# spiro.net
KiCad netlist of a schematic drawn in EAGLE
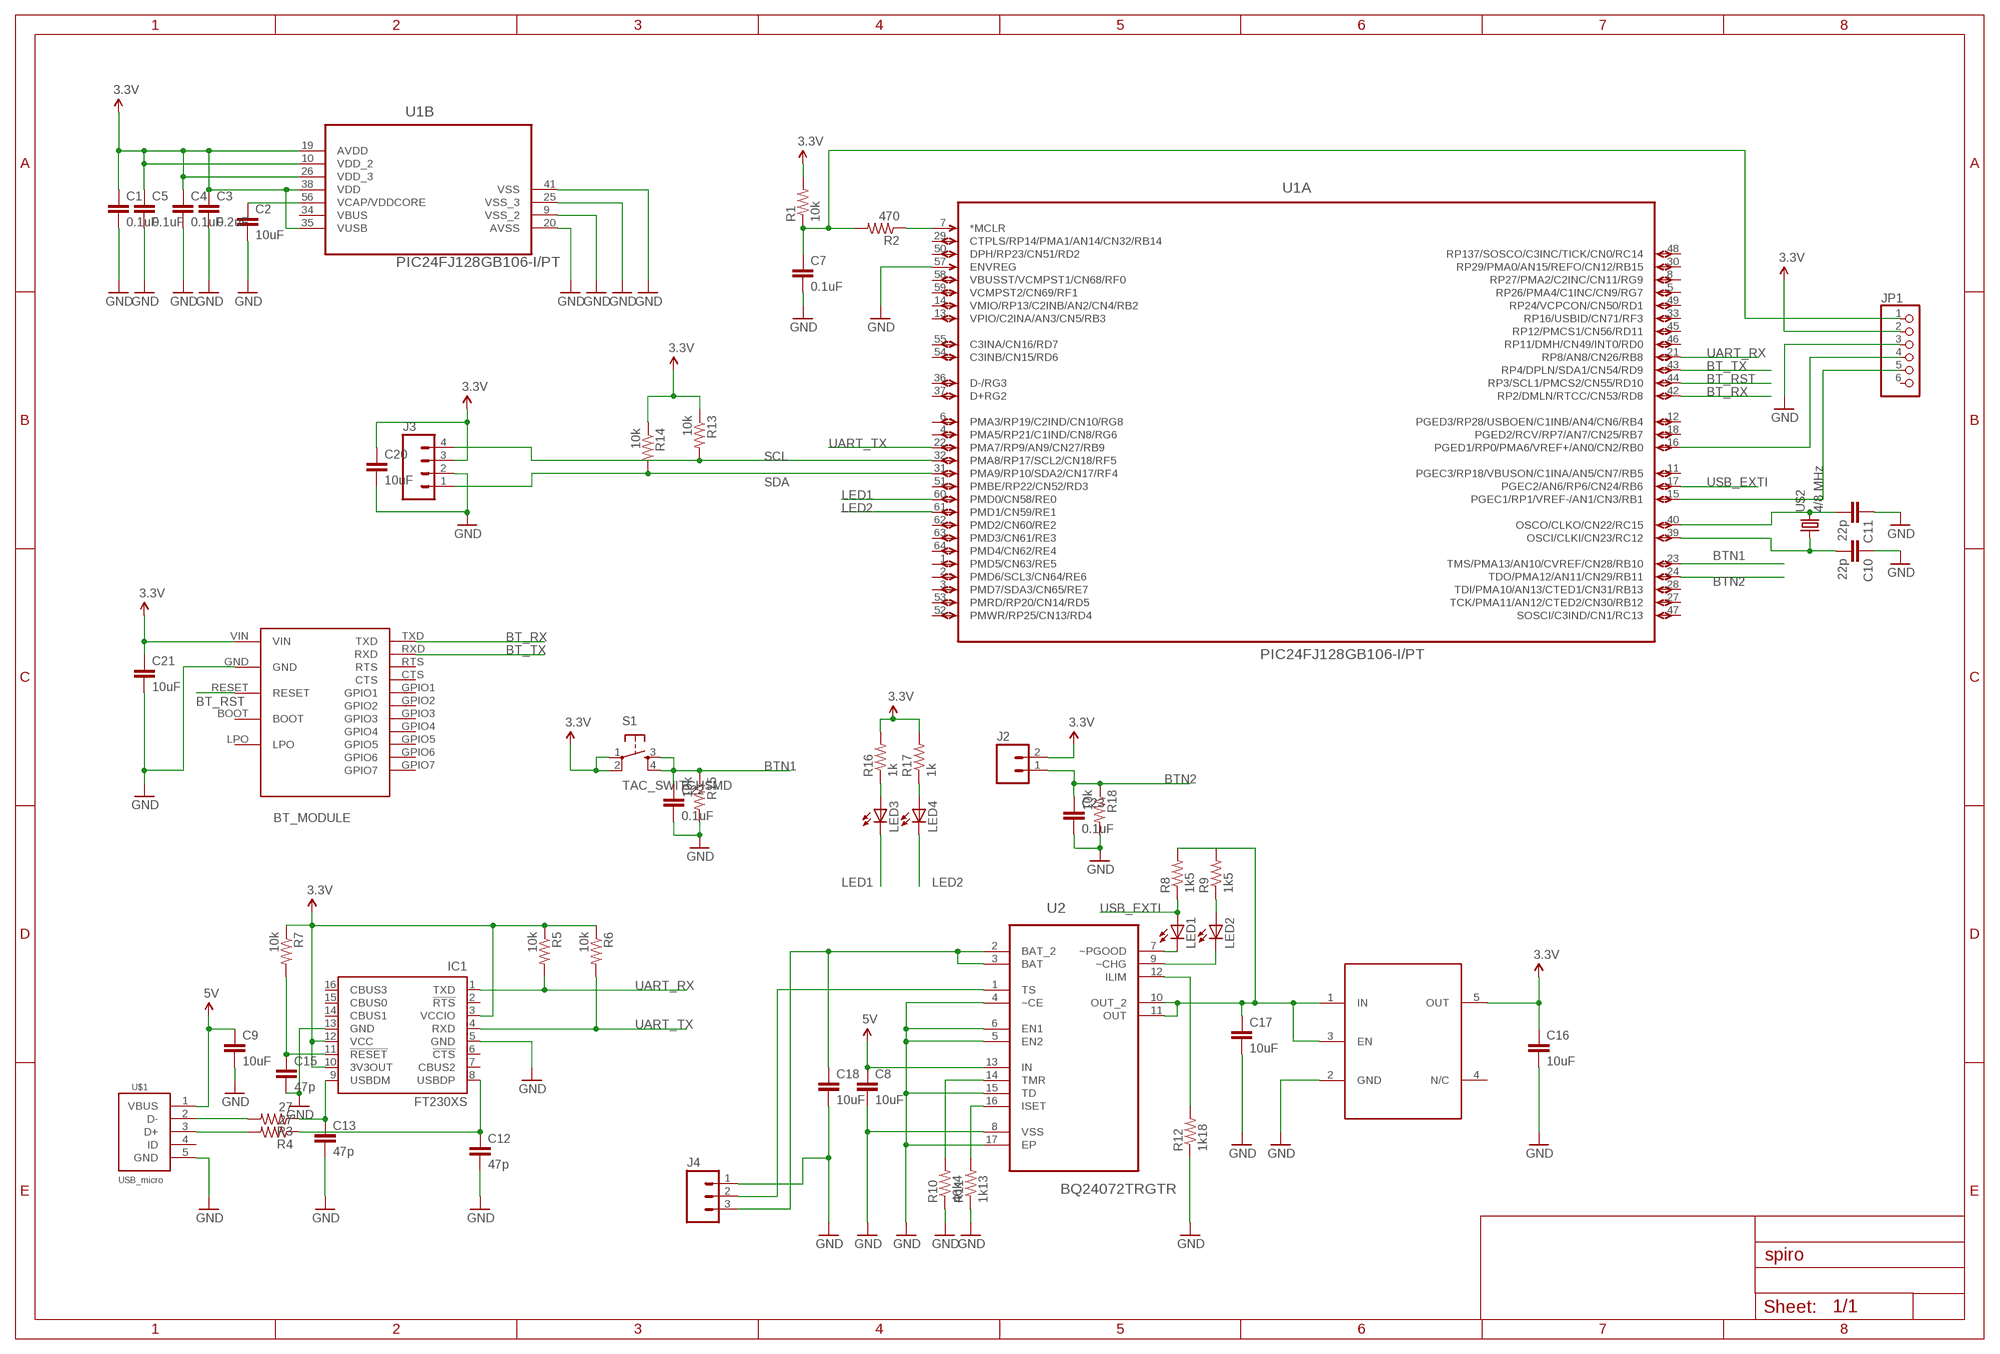
[diagram p0: schematic, sheet 1]

(export (version "E")
  (design (tool "Eeschema 10.0.6"))
  (components
    (comp (ref "BT_MODULE")
      (value "BT_MODULE")
      (footprint "eagle-import:SPBT2632C2A")
      (libsource (lib "eagle-import") (part "SPBT2632C2A"))
    )
    (comp (ref "C1")
      (value "0.1uF")
      (footprint "eagle-import:0603-CAP")
      (libsource (lib "eagle-import") (part "0.1UF-25V(+80/-20%)(0603)"))
    )
    (comp (ref "C2")
      (value "10uF")
      (footprint "eagle-import:1206")
      (libsource (lib "eagle-import") (part "10UF-6.3V-20%(1206)"))
    )
    (comp (ref "C3")
      (value "0.2uF")
      (footprint "eagle-import:0603-CAP")
      (libsource (lib "eagle-import") (part "0.1UF-25V(+80/-20%)(0603)"))
    )
    (comp (ref "C4")
      (value "0.1uF")
      (footprint "eagle-import:0603-CAP")
      (libsource (lib "eagle-import") (part "0.1UF-25V(+80/-20%)(0603)"))
    )
    (comp (ref "C5")
      (value "0.1uF")
      (footprint "eagle-import:0603-CAP")
      (libsource (lib "eagle-import") (part "0.1UF-25V(+80/-20%)(0603)"))
    )
    (comp (ref "C7")
      (value "0.1uF")
      (footprint "eagle-import:0603-CAP")
      (libsource (lib "eagle-import") (part "0.1UF-25V(+80/-20%)(0603)"))
    )
    (comp (ref "C8")
      (value "10uF")
      (footprint "eagle-import:1206")
      (libsource (lib "eagle-import") (part "10UF-6.3V-20%(1206)"))
    )
    (comp (ref "C9")
      (value "10uF")
      (footprint "eagle-import:1206")
      (libsource (lib "eagle-import") (part "10UF-6.3V-20%(1206)"))
    )
    (comp (ref "C10")
      (value "22p")
      (footprint "eagle-import:0603-CAP")
      (libsource (lib "eagle-import") (part "0.1UF-25V(+80/-20%)(0603)"))
    )
    (comp (ref "C11")
      (value "22p")
      (footprint "eagle-import:0603-CAP")
      (libsource (lib "eagle-import") (part "0.1UF-25V(+80/-20%)(0603)"))
    )
    (comp (ref "C12")
      (value "47p")
      (footprint "eagle-import:0603-CAP")
      (libsource (lib "eagle-import") (part "0.1UF-25V(+80/-20%)(0603)"))
    )
    (comp (ref "C13")
      (value "47p")
      (footprint "eagle-import:0603-CAP")
      (libsource (lib "eagle-import") (part "0.1UF-25V(+80/-20%)(0603)"))
    )
    (comp (ref "C15")
      (value "47p")
      (footprint "eagle-import:0603-CAP")
      (libsource (lib "eagle-import") (part "0.1UF-25V(+80/-20%)(0603)"))
    )
    (comp (ref "C16")
      (value "10uF")
      (footprint "eagle-import:1206")
      (libsource (lib "eagle-import") (part "10UF-6.3V-20%(1206)"))
    )
    (comp (ref "C17")
      (value "10uF")
      (footprint "eagle-import:1206")
      (libsource (lib "eagle-import") (part "10UF-6.3V-20%(1206)"))
    )
    (comp (ref "C18")
      (value "10uF")
      (footprint "eagle-import:1206")
      (libsource (lib "eagle-import") (part "10UF-6.3V-20%(1206)"))
    )
    (comp (ref "C20")
      (value "10uF")
      (footprint "eagle-import:1206")
      (libsource (lib "eagle-import") (part "10UF-6.3V-20%(1206)"))
    )
    (comp (ref "C21")
      (value "10uF")
      (footprint "eagle-import:1206")
      (libsource (lib "eagle-import") (part "10UF-6.3V-20%(1206)"))
    )
    (comp (ref "C22")
      (value "0.1uF")
      (footprint "eagle-import:0603-CAP")
      (libsource (lib "eagle-import") (part "0.1UF-25V(+80/-20%)(0603)"))
    )
    (comp (ref "C23")
      (value "0.1uF")
      (footprint "eagle-import:0603-CAP")
      (libsource (lib "eagle-import") (part "0.1UF-25V(+80/-20%)(0603)"))
    )
    (comp (ref "IC1")
      (value "FT230XS")
      (footprint "eagle-import:SSOP16")
      (libsource (lib "eagle-import") (part "FT230XS"))
    )
    (comp (ref "J2")
      (value "M02PTH")
      (footprint "eagle-import:1X02")
      (libsource (lib "eagle-import") (part "M02PTH"))
    )
    (comp (ref "J3")
      (value "M04NO_SILK_ALL_ROUND")
      (footprint "eagle-import:1X04_NO_SILK_ALL_ROUND")
      (libsource (lib "eagle-import") (part "M04NO_SILK_ALL_ROUND"))
    )
    (comp (ref "J4")
      (value "M03")
      (footprint "eagle-import:1X03-SMD-50MILS")
      (libsource (lib "eagle-import") (part "M03"))
    )
    (comp (ref "JP1")
      (value "PINHD-1X6")
      (footprint "eagle-import:1X06")
      (libsource (lib "eagle-import") (part "PINHD-1X6"))
    )
    (comp (ref "LED1")
      (value "LEDCHIP-LED0603")
      (footprint "eagle-import:CHIP-LED0603")
      (libsource (lib "eagle-import") (part "LEDCHIP-LED0603"))
    )
    (comp (ref "LED2")
      (value "LEDCHIP-LED0603")
      (footprint "eagle-import:CHIP-LED0603")
      (libsource (lib "eagle-import") (part "LEDCHIP-LED0603"))
    )
    (comp (ref "LED3")
      (value "LEDCHIP-LED0603")
      (footprint "eagle-import:CHIP-LED0603")
      (libsource (lib "eagle-import") (part "LEDCHIP-LED0603"))
    )
    (comp (ref "LED4")
      (value "LEDCHIP-LED0603")
      (footprint "eagle-import:CHIP-LED0603")
      (libsource (lib "eagle-import") (part "LEDCHIP-LED0603"))
    )
    (comp (ref "R1")
      (value "10k")
      (footprint "eagle-import:0603-RES")
      (libsource (lib "eagle-import") (part "RESISTOR0603-RES"))
    )
    (comp (ref "R2")
      (value "470")
      (footprint "eagle-import:0603-RES")
      (libsource (lib "eagle-import") (part "RESISTOR0603-RES"))
    )
    (comp (ref "R3")
      (value "27")
      (footprint "eagle-import:0603-RES")
      (libsource (lib "eagle-import") (part "RESISTOR0603-RES"))
    )
    (comp (ref "R4")
      (value "27")
      (footprint "eagle-import:0603-RES")
      (libsource (lib "eagle-import") (part "RESISTOR0603-RES"))
    )
    (comp (ref "R5")
      (value "10k")
      (footprint "eagle-import:0603-RES")
      (libsource (lib "eagle-import") (part "RESISTOR0603-RES"))
    )
    (comp (ref "R6")
      (value "10k")
      (footprint "eagle-import:0603-RES")
      (libsource (lib "eagle-import") (part "RESISTOR0603-RES"))
    )
    (comp (ref "R7")
      (value "10k")
      (footprint "eagle-import:0603-RES")
      (libsource (lib "eagle-import") (part "RESISTOR0603-RES"))
    )
    (comp (ref "R8")
      (value "1k5")
      (footprint "eagle-import:0603-RES")
      (libsource (lib "eagle-import") (part "RESISTOR0603-RES"))
    )
    (comp (ref "R9")
      (value "1k5")
      (footprint "eagle-import:0603-RES")
      (libsource (lib "eagle-import") (part "RESISTOR0603-RES"))
    )
    (comp (ref "R10")
      (value "46k4")
      (footprint "eagle-import:0603-RES")
      (libsource (lib "eagle-import") (part "RESISTOR0603-RES"))
    )
    (comp (ref "R11")
      (value "1k13")
      (footprint "eagle-import:0603-RES")
      (libsource (lib "eagle-import") (part "RESISTOR0603-RES"))
    )
    (comp (ref "R12")
      (value "1k18")
      (footprint "eagle-import:0603-RES")
      (libsource (lib "eagle-import") (part "RESISTOR0603-RES"))
    )
    (comp (ref "R13")
      (value "10k")
      (footprint "eagle-import:0603-RES")
      (libsource (lib "eagle-import") (part "RESISTOR0603-RES"))
    )
    (comp (ref "R14")
      (value "10k")
      (footprint "eagle-import:0603-RES")
      (libsource (lib "eagle-import") (part "RESISTOR0603-RES"))
    )
    (comp (ref "R15")
      (value "10k")
      (footprint "eagle-import:0603-RES")
      (libsource (lib "eagle-import") (part "RESISTOR0603-RES"))
    )
    (comp (ref "R16")
      (value "1k")
      (footprint "eagle-import:0603-RES")
      (libsource (lib "eagle-import") (part "RESISTOR0603-RES"))
    )
    (comp (ref "R17")
      (value "1k")
      (footprint "eagle-import:0603-RES")
      (libsource (lib "eagle-import") (part "RESISTOR0603-RES"))
    )
    (comp (ref "R18")
      (value "10k")
      (footprint "eagle-import:0603-RES")
      (libsource (lib "eagle-import") (part "RESISTOR0603-RES"))
    )
    (comp (ref "S1")
      (value "TAC_SWITCHSMD")
      (footprint "eagle-import:TACTILE-SWITCH-SMD")
      (libsource (lib "eagle-import") (part "TAC_SWITCHSMD"))
    )
    (comp (ref "U$1")
      (value "USB_micro")
      (footprint "eagle-import:USB-MICRO-MOLEX-105017-0001")
      (libsource (lib "eagle-import") (part "USB-CON-5PIN-105017-0001"))
    )
    (comp (ref "U$2")
      (value "4/8 MHz")
      (footprint "eagle-import:CRYSTAL-SMD-6X3.5-2SMX")
      (libsource (lib "eagle-import") (part "CRYSTAL-2SMX"))
    )
    (comp (ref "U$3")
      (value "LP3990")
      (footprint "eagle-import:SOT95P280X145-5N")
      (libsource (lib "eagle-import") (part "LP3990"))
    )
    (comp (ref "U1")
      (value "PIC24FJ128GB106-I/PT")
      (footprint "eagle-import:QFP50P1200X1200X120-64N")
      (fields (field (name "MPN") "PIC24FJ128Gb106-I/PT"))
      (libsource (lib "eagle-import") (part "PIC24FJ128GB106-I/PT"))
    )
    (comp (ref "U2")
      (value "BQ24072TRGTR")
      (footprint "eagle-import:QFN50P300X300X100-17N")
      (libsource (lib "eagle-import") (part "BQ24072TRGTR"))
    )
  )
  (nets
    (net (code "1") (name "/BTN1") (class "Default")
      (node (ref "C22") (pin "1") (pinfunction "1_1") (pintype "passive"))
      (node (ref "R15") (pin "1") (pinfunction "1_1") (pintype "passive"))
      (node (ref "S1") (pin "3") (pinfunction "3_3") (pintype "passive"))
      (node (ref "S1") (pin "4") (pinfunction "4_4") (pintype "passive"))
      (node (ref "U1") (pin "23") (pinfunction "TMS/PMA13/AN10/CVREF/CN28/RB10_23") (pintype "bidirectional"))
    )
    (net (code "2") (name "/BTN2") (class "Default")
      (node (ref "C23") (pin "1") (pinfunction "1_1") (pintype "passive"))
      (node (ref "J2") (pin "1") (pinfunction "1_1") (pintype "passive"))
      (node (ref "R18") (pin "1") (pinfunction "1_1") (pintype "passive"))
      (node (ref "U1") (pin "24") (pinfunction "TDO/PMA12/AN11/CN29/RB11_24") (pintype "bidirectional"))
    )
    (net (code "3") (name "/BT_RST") (class "Default")
      (node (ref "BT_MODULE") (pin "RESET") (pinfunction "RESET_RESET") (pintype "bidirectional"))
      (node (ref "U1") (pin "44") (pinfunction "RP3/SCL1/PMCS2/CN55/RD10_44") (pintype "bidirectional"))
    )
    (net (code "4") (name "/BT_RX") (class "Default")
      (node (ref "BT_MODULE") (pin "TXD") (pinfunction "TXD_TXD") (pintype "bidirectional"))
      (node (ref "U1") (pin "42") (pinfunction "RP2/DMLN/RTCC/CN53/RD8_42") (pintype "bidirectional"))
    )
    (net (code "5") (name "/BT_TX") (class "Default")
      (node (ref "BT_MODULE") (pin "RXD") (pinfunction "RXD_RXD") (pintype "bidirectional"))
      (node (ref "U1") (pin "43") (pinfunction "RP4/DPLN/SDA1/CN54/RD9_43") (pintype "bidirectional"))
    )
    (net (code "6") (name "/LED1") (class "Default")
      (node (ref "LED3") (pin "C") (pinfunction "C_C") (pintype "passive"))
      (node (ref "U1") (pin "60") (pinfunction "PMD0/CN58/RE0_60") (pintype "bidirectional"))
    )
    (net (code "7") (name "/LED2") (class "Default")
      (node (ref "LED4") (pin "C") (pinfunction "C_C") (pintype "passive"))
      (node (ref "U1") (pin "61") (pinfunction "PMD1/CN59/RE1_61") (pintype "bidirectional"))
    )
    (net (code "8") (name "/SCL") (class "Default")
      (node (ref "J3") (pin "4") (pinfunction "4_4") (pintype "passive"))
      (node (ref "R13") (pin "2") (pinfunction "2_2") (pintype "passive"))
      (node (ref "U1") (pin "32") (pinfunction "PMA8/RP17/SCL2/CN18/RF5_32") (pintype "bidirectional"))
    )
    (net (code "9") (name "/SDA") (class "Default")
      (node (ref "J3") (pin "1") (pinfunction "1_1") (pintype "passive"))
      (node (ref "R14") (pin "2") (pinfunction "2_2") (pintype "passive"))
      (node (ref "U1") (pin "31") (pinfunction "PMA9/RP10/SDA2/CN17/RF4_31") (pintype "bidirectional"))
    )
    (net (code "10") (name "/UART_RX") (class "Default")
      (node (ref "IC1") (pin "1") (pinfunction "TXD_1") (pintype "output"))
      (node (ref "R5") (pin "2") (pinfunction "2_2") (pintype "passive"))
      (node (ref "U1") (pin "21") (pinfunction "RP8/AN8/CN26/RB8_21") (pintype "bidirectional"))
    )
    (net (code "11") (name "/UART_TX") (class "Default")
      (node (ref "IC1") (pin "4") (pinfunction "RXD_4") (pintype "input"))
      (node (ref "R6") (pin "2") (pinfunction "2_2") (pintype "passive"))
      (node (ref "U1") (pin "22") (pinfunction "PMA7/RP9/AN9/CN27/RB9_22") (pintype "bidirectional"))
    )
    (net (code "12") (name "/USB_EXTI") (class "Default")
      (node (ref "LED1") (pin "A") (pinfunction "A_A") (pintype "passive"))
      (node (ref "R8") (pin "1") (pinfunction "1_1") (pintype "passive"))
      (node (ref "U1") (pin "17") (pinfunction "PGEC2/AN6/RP6/CN24/RB6_17") (pintype "bidirectional"))
    )
    (net (code "13") (name "/VBUS") (class "Default")
      (node (ref "U1") (pin "34") (pinfunction "VBUS_34") (pintype "power_in"))
    )
    (net (code "14") (name "3.3V") (class "Default")
      (node (ref "BT_MODULE") (pin "VIN") (pinfunction "VIN_VIN") (pintype "bidirectional"))
      (node (ref "C1") (pin "1") (pinfunction "1_1") (pintype "passive"))
      (node (ref "C16") (pin "1") (pinfunction "1_1") (pintype "passive"))
      (node (ref "C20") (pin "1") (pinfunction "1_1") (pintype "passive"))
      (node (ref "C21") (pin "1") (pinfunction "1_1") (pintype "passive"))
      (node (ref "C3") (pin "1") (pinfunction "1_1") (pintype "passive"))
      (node (ref "C4") (pin "1") (pinfunction "1_1") (pintype "passive"))
      (node (ref "C5") (pin "1") (pinfunction "1_1") (pintype "passive"))
      (node (ref "IC1") (pin "10") (pinfunction "3V3OUT_10") (pintype "output"))
      (node (ref "IC1") (pin "12") (pinfunction "VCC_12") (pintype "power_in"))
      (node (ref "IC1") (pin "3") (pinfunction "VCCIO_3") (pintype "power_in"))
      (node (ref "J2") (pin "2") (pinfunction "2_2") (pintype "passive"))
      (node (ref "J3") (pin "3") (pinfunction "3_3") (pintype "passive"))
      (node (ref "JP1") (pin "2") (pinfunction "2_2") (pintype "passive"))
      (node (ref "R1") (pin "2") (pinfunction "2_2") (pintype "passive"))
      (node (ref "R13") (pin "1") (pinfunction "1_1") (pintype "passive"))
      (node (ref "R14") (pin "1") (pinfunction "1_1") (pintype "passive"))
      (node (ref "R16") (pin "2") (pinfunction "2_2") (pintype "passive"))
      (node (ref "R17") (pin "2") (pinfunction "2_2") (pintype "passive"))
      (node (ref "R5") (pin "1") (pinfunction "1_1") (pintype "passive"))
      (node (ref "R6") (pin "1") (pinfunction "1_1") (pintype "passive"))
      (node (ref "R7") (pin "1") (pinfunction "1_1") (pintype "passive"))
      (node (ref "S1") (pin "1") (pinfunction "1_1") (pintype "passive"))
      (node (ref "S1") (pin "2") (pinfunction "2_2") (pintype "passive"))
      (node (ref "U$3") (pin "5") (pinfunction "OUT_5") (pintype "bidirectional"))
      (node (ref "U1") (pin "10") (pinfunction "VDD_2_10") (pintype "power_in"))
      (node (ref "U1") (pin "19") (pinfunction "AVDD_19") (pintype "power_in"))
      (node (ref "U1") (pin "26") (pinfunction "VDD_3_26") (pintype "power_in"))
      (node (ref "U1") (pin "35") (pinfunction "VUSB_35") (pintype "power_in"))
      (node (ref "U1") (pin "38") (pinfunction "VDD_38") (pintype "power_in"))
    )
    (net (code "15") (name "5V") (class "Default")
      (node (ref "C8") (pin "1") (pinfunction "1_1") (pintype "passive"))
      (node (ref "C9") (pin "1") (pinfunction "1_1") (pintype "passive"))
      (node (ref "U$1") (pin "1") (pinfunction "VBUS_1") (pintype "power_in"))
      (node (ref "U2") (pin "13") (pinfunction "IN_13") (pintype "input"))
    )
    (net (code "16") (name "GND") (class "Default")
      (node (ref "BT_MODULE") (pin "GND") (pinfunction "GND_GND") (pintype "bidirectional"))
      (node (ref "C1") (pin "2") (pinfunction "2_2") (pintype "passive"))
      (node (ref "C10") (pin "1") (pinfunction "1_1") (pintype "passive"))
      (node (ref "C11") (pin "1") (pinfunction "1_1") (pintype "passive"))
      (node (ref "C12") (pin "2") (pinfunction "2_2") (pintype "passive"))
      (node (ref "C13") (pin "2") (pinfunction "2_2") (pintype "passive"))
      (node (ref "C15") (pin "2") (pinfunction "2_2") (pintype "passive"))
      (node (ref "C16") (pin "2") (pinfunction "2_2") (pintype "passive"))
      (node (ref "C17") (pin "2") (pinfunction "2_2") (pintype "passive"))
      (node (ref "C18") (pin "2") (pinfunction "2_2") (pintype "passive"))
      (node (ref "C2") (pin "2") (pinfunction "2_2") (pintype "passive"))
      (node (ref "C20") (pin "2") (pinfunction "2_2") (pintype "passive"))
      (node (ref "C21") (pin "2") (pinfunction "2_2") (pintype "passive"))
      (node (ref "C22") (pin "2") (pinfunction "2_2") (pintype "passive"))
      (node (ref "C23") (pin "2") (pinfunction "2_2") (pintype "passive"))
      (node (ref "C3") (pin "2") (pinfunction "2_2") (pintype "passive"))
      (node (ref "C4") (pin "2") (pinfunction "2_2") (pintype "passive"))
      (node (ref "C5") (pin "2") (pinfunction "2_2") (pintype "passive"))
      (node (ref "C7") (pin "2") (pinfunction "2_2") (pintype "passive"))
      (node (ref "C8") (pin "2") (pinfunction "2_2") (pintype "passive"))
      (node (ref "C9") (pin "2") (pinfunction "2_2") (pintype "passive"))
      (node (ref "IC1") (pin "13") (pinfunction "GND_13") (pintype "power_in"))
      (node (ref "IC1") (pin "5") (pinfunction "GND_5") (pintype "power_in"))
      (node (ref "J3") (pin "2") (pinfunction "2_2") (pintype "passive"))
      (node (ref "J4") (pin "1") (pinfunction "3_1") (pintype "passive"))
      (node (ref "JP1") (pin "3") (pinfunction "3_3") (pintype "passive"))
      (node (ref "R10") (pin "1") (pinfunction "1_1") (pintype "passive"))
      (node (ref "R11") (pin "1") (pinfunction "1_1") (pintype "passive"))
      (node (ref "R12") (pin "1") (pinfunction "1_1") (pintype "passive"))
      (node (ref "R15") (pin "2") (pinfunction "2_2") (pintype "passive"))
      (node (ref "R18") (pin "2") (pinfunction "2_2") (pintype "passive"))
      (node (ref "U$1") (pin "5") (pinfunction "GND_5") (pintype "power_in"))
      (node (ref "U$3") (pin "2") (pinfunction "GND_2") (pintype "bidirectional"))
      (node (ref "U1") (pin "20") (pinfunction "AVSS_20") (pintype "power_in"))
      (node (ref "U1") (pin "25") (pinfunction "VSS_3_25") (pintype "power_in"))
      (node (ref "U1") (pin "41") (pinfunction "VSS_41") (pintype "power_in"))
      (node (ref "U1") (pin "57") (pinfunction "ENVREG_57") (pintype "input"))
      (node (ref "U1") (pin "9") (pinfunction "VSS_2_9") (pintype "power_in"))
      (node (ref "U2") (pin "15") (pinfunction "TD_15") (pintype "input"))
      (node (ref "U2") (pin "17") (pinfunction "EP_17") (pintype "passive"))
      (node (ref "U2") (pin "4") (pinfunction "~{CE}_4") (pintype "input"))
      (node (ref "U2") (pin "5") (pinfunction "EN2_5") (pintype "input"))
      (node (ref "U2") (pin "6") (pinfunction "EN1_6") (pintype "input"))
      (node (ref "U2") (pin "8") (pinfunction "VSS_8") (pintype "passive"))
    )
    (net (code "17") (name "Net-(C7-Pad1)") (class "Default")
      (node (ref "C7") (pin "1") (pinfunction "1_1") (pintype "passive"))
      (node (ref "JP1") (pin "1") (pinfunction "1_1") (pintype "passive"))
      (node (ref "R1") (pin "1") (pinfunction "1_1") (pintype "passive"))
      (node (ref "R2") (pin "2") (pinfunction "2_2") (pintype "passive"))
    )
    (net (code "18") (name "Net-(IC1-USBDM)") (class "Default")
      (node (ref "C13") (pin "1") (pinfunction "1_1") (pintype "passive"))
      (node (ref "IC1") (pin "9") (pinfunction "USBDM_9") (pintype "input"))
      (node (ref "R3") (pin "1") (pinfunction "1_1") (pintype "passive"))
    )
    (net (code "19") (name "Net-(IC1-USBDP)") (class "Default")
      (node (ref "C12") (pin "1") (pinfunction "1_1") (pintype "passive"))
      (node (ref "IC1") (pin "8") (pinfunction "USBDP_8") (pintype "input"))
      (node (ref "R4") (pin "1") (pinfunction "1_1") (pintype "passive"))
    )
    (net (code "20") (name "Net-(IC1-~{RESET})") (class "Default")
      (node (ref "C15") (pin "1") (pinfunction "1_1") (pintype "passive"))
      (node (ref "IC1") (pin "11") (pinfunction "~{RESET}_11") (pintype "input"))
      (node (ref "R7") (pin "2") (pinfunction "2_2") (pintype "passive"))
    )
    (net (code "21") (name "Net-(J4-1)") (class "Default")
      (node (ref "C18") (pin "1") (pinfunction "1_1") (pintype "passive"))
      (node (ref "J4") (pin "3") (pinfunction "1_3") (pintype "passive"))
      (node (ref "U2") (pin "2") (pinfunction "BAT_2_2") (pintype "bidirectional"))
      (node (ref "U2") (pin "3") (pinfunction "BAT_3") (pintype "bidirectional"))
    )
    (net (code "22") (name "Net-(LED2-PadA)") (class "Default")
      (node (ref "LED2") (pin "A") (pinfunction "A_A") (pintype "passive"))
      (node (ref "R9") (pin "1") (pinfunction "1_1") (pintype "passive"))
    )
    (net (code "23") (name "Net-(LED3-PadA)") (class "Default")
      (node (ref "LED3") (pin "A") (pinfunction "A_A") (pintype "passive"))
      (node (ref "R16") (pin "1") (pinfunction "1_1") (pintype "passive"))
    )
    (net (code "24") (name "Net-(LED4-PadA)") (class "Default")
      (node (ref "LED4") (pin "A") (pinfunction "A_A") (pintype "passive"))
      (node (ref "R17") (pin "1") (pinfunction "1_1") (pintype "passive"))
    )
    (net (code "25") (name "Net-(U$1-D+)") (class "Default")
      (node (ref "R4") (pin "2") (pinfunction "2_2") (pintype "passive"))
      (node (ref "U$1") (pin "3") (pinfunction "D+_3") (pintype "bidirectional"))
    )
    (net (code "26") (name "Net-(U$1-D-)") (class "Default")
      (node (ref "R3") (pin "2") (pinfunction "2_2") (pintype "passive"))
      (node (ref "U$1") (pin "2") (pinfunction "D-_2") (pintype "bidirectional"))
    )
    (net (code "27") (name "Net-(U$2-1)") (class "Default")
      (node (ref "C10") (pin "2") (pinfunction "2_2") (pintype "passive"))
      (node (ref "U$2") (pin "P$1") (pinfunction "1_P$1") (pintype "passive"))
      (node (ref "U1") (pin "39") (pinfunction "OSCI/CLKI/CN23/RC12_39") (pintype "bidirectional"))
    )
    (net (code "28") (name "Net-(U$2-2)") (class "Default")
      (node (ref "C11") (pin "2") (pinfunction "2_2") (pintype "passive"))
      (node (ref "U$2") (pin "P$3") (pinfunction "2_P$3") (pintype "passive"))
      (node (ref "U1") (pin "40") (pinfunction "OSCO/CLKO/CN22/RC15_40") (pintype "bidirectional"))
    )
    (net (code "29") (name "Net-(U$3-EN)") (class "Default")
      (node (ref "C17") (pin "1") (pinfunction "1_1") (pintype "passive"))
      (node (ref "R8") (pin "2") (pinfunction "2_2") (pintype "passive"))
      (node (ref "R9") (pin "2") (pinfunction "2_2") (pintype "passive"))
      (node (ref "U$3") (pin "1") (pinfunction "IN_1") (pintype "bidirectional"))
      (node (ref "U$3") (pin "3") (pinfunction "EN_3") (pintype "bidirectional"))
      (node (ref "U2") (pin "10") (pinfunction "OUT_2_10") (pintype "output"))
      (node (ref "U2") (pin "11") (pinfunction "OUT_11") (pintype "output"))
    )
    (net (code "30") (name "Net-(U1A-*MCLR)") (class "Default")
      (node (ref "R2") (pin "1") (pinfunction "1_1") (pintype "passive"))
      (node (ref "U1") (pin "7") (pinfunction "*MCLR_7") (pintype "input"))
    )
    (net (code "31") (name "Net-(U1A-PGEC1{slash}RP1{slash}VREF-{slash}AN1{slash}CN3{slash}RB1)") (class "Default")
      (node (ref "JP1") (pin "5") (pinfunction "5_5") (pintype "passive"))
      (node (ref "U1") (pin "15") (pinfunction "PGEC1/RP1/VREF-/AN1/CN3/RB1_15") (pintype "bidirectional"))
    )
    (net (code "32") (name "Net-(U1A-PGED1{slash}RP0{slash}PMA6{slash}VREF+{slash}AN0{slash}CN2{slash}RB0)") (class "Default")
      (node (ref "JP1") (pin "4") (pinfunction "4_4") (pintype "passive"))
      (node (ref "U1") (pin "16") (pinfunction "PGED1/RP0/PMA6/VREF+/AN0/CN2/RB0_16") (pintype "bidirectional"))
    )
    (net (code "33") (name "Net-(U1B-VCAP{slash}VDDCORE)") (class "Default")
      (node (ref "C2") (pin "1") (pinfunction "1_1") (pintype "passive"))
      (node (ref "U1") (pin "56") (pinfunction "VCAP/VDDCORE_56") (pintype "power_in"))
    )
    (net (code "34") (name "Net-(U2-ILIM)") (class "Default")
      (node (ref "R12") (pin "2") (pinfunction "2_2") (pintype "passive"))
      (node (ref "U2") (pin "12") (pinfunction "ILIM_12") (pintype "output"))
    )
    (net (code "35") (name "Net-(U2-ISET)") (class "Default")
      (node (ref "R11") (pin "2") (pinfunction "2_2") (pintype "passive"))
      (node (ref "U2") (pin "16") (pinfunction "ISET_16") (pintype "bidirectional"))
    )
    (net (code "36") (name "Net-(U2-TMR)") (class "Default")
      (node (ref "R10") (pin "2") (pinfunction "2_2") (pintype "passive"))
      (node (ref "U2") (pin "14") (pinfunction "TMR_14") (pintype "input"))
    )
    (net (code "37") (name "Net-(U2-TS)") (class "Default")
      (node (ref "J4") (pin "2") (pinfunction "2_2") (pintype "passive"))
      (node (ref "U2") (pin "1") (pinfunction "TS_1") (pintype "bidirectional"))
    )
    (net (code "38") (name "Net-(U2-~{CHG})") (class "Default")
      (node (ref "LED2") (pin "C") (pinfunction "C_C") (pintype "passive"))
      (node (ref "U2") (pin "9") (pinfunction "~{CHG}_9") (pintype "output"))
    )
    (net (code "39") (name "Net-(U2-~{PGOOD})") (class "Default")
      (node (ref "LED1") (pin "C") (pinfunction "C_C") (pintype "passive"))
      (node (ref "U2") (pin "7") (pinfunction "~{PGOOD}_7") (pintype "output"))
    )
    (net (code "40") (name "unconnected-(BT_MODULE-PadBOOT)") (class "Default")
      (node (ref "BT_MODULE") (pin "BOOT") (pinfunction "BOOT_BOOT") (pintype "bidirectional"))
    )
    (net (code "41") (name "unconnected-(BT_MODULE-PadCTS)") (class "Default")
      (node (ref "BT_MODULE") (pin "CTS") (pinfunction "CTS_CTS") (pintype "bidirectional"))
    )
    (net (code "42") (name "unconnected-(BT_MODULE-PadGPIO1)") (class "Default")
      (node (ref "BT_MODULE") (pin "GPIO1") (pinfunction "GPIO1_GPIO1") (pintype "bidirectional"))
    )
    (net (code "43") (name "unconnected-(BT_MODULE-PadGPIO2)") (class "Default")
      (node (ref "BT_MODULE") (pin "GPIO2") (pinfunction "GPIO2_GPIO2") (pintype "bidirectional"))
    )
    (net (code "44") (name "unconnected-(BT_MODULE-PadGPIO3)") (class "Default")
      (node (ref "BT_MODULE") (pin "GPIO3") (pinfunction "GPIO3_GPIO3") (pintype "bidirectional"))
    )
    (net (code "45") (name "unconnected-(BT_MODULE-PadGPIO4)") (class "Default")
      (node (ref "BT_MODULE") (pin "GPIO4") (pinfunction "GPIO4_GPIO4") (pintype "bidirectional"))
    )
    (net (code "46") (name "unconnected-(BT_MODULE-PadGPIO5)") (class "Default")
      (node (ref "BT_MODULE") (pin "GPIO5") (pinfunction "GPIO5_GPIO5") (pintype "bidirectional"))
    )
    (net (code "47") (name "unconnected-(BT_MODULE-PadGPIO6)") (class "Default")
      (node (ref "BT_MODULE") (pin "GPIO6") (pinfunction "GPIO6_GPIO6") (pintype "bidirectional"))
    )
    (net (code "48") (name "unconnected-(BT_MODULE-PadGPIO7)") (class "Default")
      (node (ref "BT_MODULE") (pin "GPIO7") (pinfunction "GPIO7_GPIO7") (pintype "bidirectional"))
    )
    (net (code "49") (name "unconnected-(BT_MODULE-PadLPO)") (class "Default")
      (node (ref "BT_MODULE") (pin "LPO") (pinfunction "LPO_LPO") (pintype "bidirectional"))
    )
    (net (code "50") (name "unconnected-(BT_MODULE-PadRTS)") (class "Default")
      (node (ref "BT_MODULE") (pin "RTS") (pinfunction "RTS_RTS") (pintype "bidirectional"))
    )
    (net (code "51") (name "unconnected-(IC1-CBUS0-Pad15)") (class "Default")
      (node (ref "IC1") (pin "15") (pinfunction "CBUS0_15") (pintype "bidirectional"))
    )
    (net (code "52") (name "unconnected-(IC1-CBUS1-Pad14)") (class "Default")
      (node (ref "IC1") (pin "14") (pinfunction "CBUS1_14") (pintype "bidirectional"))
    )
    (net (code "53") (name "unconnected-(IC1-CBUS2-Pad7)") (class "Default")
      (node (ref "IC1") (pin "7") (pinfunction "CBUS2_7") (pintype "bidirectional"))
    )
    (net (code "54") (name "unconnected-(IC1-CBUS3-Pad16)") (class "Default")
      (node (ref "IC1") (pin "16") (pinfunction "CBUS3_16") (pintype "bidirectional"))
    )
    (net (code "55") (name "unconnected-(IC1-~{CTS}-Pad6)") (class "Default")
      (node (ref "IC1") (pin "6") (pinfunction "~{CTS}_6") (pintype "input"))
    )
    (net (code "56") (name "unconnected-(IC1-~{RTS}-Pad2)") (class "Default")
      (node (ref "IC1") (pin "2") (pinfunction "~{RTS}_2") (pintype "output"))
    )
    (net (code "57") (name "unconnected-(JP1-Pad6)") (class "Default")
      (node (ref "JP1") (pin "6") (pinfunction "6_6") (pintype "passive"))
    )
    (net (code "58") (name "unconnected-(U$1-ID-Pad4)") (class "Default")
      (node (ref "U$1") (pin "4") (pinfunction "ID_4") (pintype "bidirectional"))
    )
    (net (code "59") (name "unconnected-(U$3-N{slash}C-Pad4)") (class "Default")
      (node (ref "U$3") (pin "4") (pinfunction "N/C_4") (pintype "bidirectional"))
    )
    (net (code "60") (name "unconnected-(U1A-C3INA{slash}CN16{slash}RD7-Pad55)") (class "Default")
      (node (ref "U1") (pin "55") (pinfunction "C3INA/CN16/RD7_55") (pintype "bidirectional"))
    )
    (net (code "61") (name "unconnected-(U1A-C3INB{slash}CN15{slash}RD6-Pad54)") (class "Default")
      (node (ref "U1") (pin "54") (pinfunction "C3INB/CN15/RD6_54") (pintype "bidirectional"))
    )
    (net (code "62") (name "unconnected-(U1A-CTPLS{slash}RP14{slash}PMA1{slash}AN14{slash}CN32{slash}RB14-Pad29)") (class "Default")
      (node (ref "U1") (pin "29") (pinfunction "CTPLS/RP14/PMA1/AN14/CN32/RB14_29") (pintype "bidirectional"))
    )
    (net (code "63") (name "unconnected-(U1A-D+RG2-Pad37)") (class "Default")
      (node (ref "U1") (pin "37") (pinfunction "D+RG2_37") (pintype "bidirectional"))
    )
    (net (code "64") (name "unconnected-(U1A-D-{slash}RG3-Pad36)") (class "Default")
      (node (ref "U1") (pin "36") (pinfunction "D-/RG3_36") (pintype "bidirectional"))
    )
    (net (code "65") (name "unconnected-(U1A-DPH{slash}RP23{slash}CN51{slash}RD2-Pad50)") (class "Default")
      (node (ref "U1") (pin "50") (pinfunction "DPH/RP23/CN51/RD2_50") (pintype "bidirectional"))
    )
    (net (code "66") (name "unconnected-(U1A-PGEC3{slash}RP18{slash}VBUSON{slash}C1INA{slash}AN5{slash}CN7{slash}RB5-Pad11)") (class "Default")
      (node (ref "U1") (pin "11") (pinfunction "PGEC3/RP18/VBUSON/C1INA/AN5/CN7/RB5_11") (pintype "bidirectional"))
    )
    (net (code "67") (name "unconnected-(U1A-PGED2{slash}RCV{slash}RP7{slash}AN7{slash}CN25{slash}RB7-Pad18)") (class "Default")
      (node (ref "U1") (pin "18") (pinfunction "PGED2/RCV/RP7/AN7/CN25/RB7_18") (pintype "bidirectional"))
    )
    (net (code "68") (name "unconnected-(U1A-PGED3{slash}RP28{slash}USBOEN{slash}C1INB{slash}AN4{slash}CN6{slash}RB4-Pad12)") (class "Default")
      (node (ref "U1") (pin "12") (pinfunction "PGED3/RP28/USBOEN/C1INB/AN4/CN6/RB4_12") (pintype "bidirectional"))
    )
    (net (code "69") (name "unconnected-(U1A-PMA3{slash}RP19{slash}C2IND{slash}CN10{slash}RG8-Pad6)") (class "Default")
      (node (ref "U1") (pin "6") (pinfunction "PMA3/RP19/C2IND/CN10/RG8_6") (pintype "bidirectional"))
    )
    (net (code "70") (name "unconnected-(U1A-PMA5{slash}RP21{slash}C1IND{slash}CN8{slash}RG6-Pad4)") (class "Default")
      (node (ref "U1") (pin "4") (pinfunction "PMA5/RP21/C1IND/CN8/RG6_4") (pintype "bidirectional"))
    )
    (net (code "71") (name "unconnected-(U1A-PMBE{slash}RP22{slash}CN52{slash}RD3-Pad51)") (class "Default")
      (node (ref "U1") (pin "51") (pinfunction "PMBE/RP22/CN52/RD3_51") (pintype "bidirectional"))
    )
    (net (code "72") (name "unconnected-(U1A-PMD2{slash}CN60{slash}RE2-Pad62)") (class "Default")
      (node (ref "U1") (pin "62") (pinfunction "PMD2/CN60/RE2_62") (pintype "bidirectional"))
    )
    (net (code "73") (name "unconnected-(U1A-PMD3{slash}CN61{slash}RE3-Pad63)") (class "Default")
      (node (ref "U1") (pin "63") (pinfunction "PMD3/CN61/RE3_63") (pintype "bidirectional"))
    )
    (net (code "74") (name "unconnected-(U1A-PMD4{slash}CN62{slash}RE4-Pad64)") (class "Default")
      (node (ref "U1") (pin "64") (pinfunction "PMD4/CN62/RE4_64") (pintype "bidirectional"))
    )
    (net (code "75") (name "unconnected-(U1A-PMD5{slash}CN63{slash}RE5-Pad1)") (class "Default")
      (node (ref "U1") (pin "1") (pinfunction "PMD5/CN63/RE5_1") (pintype "bidirectional"))
    )
    (net (code "76") (name "unconnected-(U1A-PMD6{slash}SCL3{slash}CN64{slash}RE6-Pad2)") (class "Default")
      (node (ref "U1") (pin "2") (pinfunction "PMD6/SCL3/CN64/RE6_2") (pintype "bidirectional"))
    )
    (net (code "77") (name "unconnected-(U1A-PMD7{slash}SDA3{slash}CN65{slash}RE7-Pad3)") (class "Default")
      (node (ref "U1") (pin "3") (pinfunction "PMD7/SDA3/CN65/RE7_3") (pintype "bidirectional"))
    )
    (net (code "78") (name "unconnected-(U1A-PMRD{slash}RP20{slash}CN14{slash}RD5-Pad53)") (class "Default")
      (node (ref "U1") (pin "53") (pinfunction "PMRD/RP20/CN14/RD5_53") (pintype "bidirectional"))
    )
    (net (code "79") (name "unconnected-(U1A-PMWR{slash}RP25{slash}CN13{slash}RD4-Pad52)") (class "Default")
      (node (ref "U1") (pin "52") (pinfunction "PMWR/RP25/CN13/RD4_52") (pintype "bidirectional"))
    )
    (net (code "80") (name "unconnected-(U1A-RP11{slash}DMH{slash}CN49{slash}INT0{slash}RD0-Pad46)") (class "Default")
      (node (ref "U1") (pin "46") (pinfunction "RP11/DMH/CN49/INT0/RD0_46") (pintype "bidirectional"))
    )
    (net (code "81") (name "unconnected-(U1A-RP12{slash}PMCS1{slash}CN56{slash}RD11-Pad45)") (class "Default")
      (node (ref "U1") (pin "45") (pinfunction "RP12/PMCS1/CN56/RD11_45") (pintype "bidirectional"))
    )
    (net (code "82") (name "unconnected-(U1A-RP16{slash}USBID{slash}CN71{slash}RF3-Pad33)") (class "Default")
      (node (ref "U1") (pin "33") (pinfunction "RP16/USBID/CN71/RF3_33") (pintype "bidirectional"))
    )
    (net (code "83") (name "unconnected-(U1A-RP24{slash}VCPCON{slash}CN50{slash}RD1-Pad49)") (class "Default")
      (node (ref "U1") (pin "49") (pinfunction "RP24/VCPCON/CN50/RD1_49") (pintype "bidirectional"))
    )
    (net (code "84") (name "unconnected-(U1A-RP26{slash}PMA4{slash}C1INC{slash}CN9{slash}RG7-Pad5)") (class "Default")
      (node (ref "U1") (pin "5") (pinfunction "RP26/PMA4/C1INC/CN9/RG7_5") (pintype "bidirectional"))
    )
    (net (code "85") (name "unconnected-(U1A-RP27{slash}PMA2{slash}C2INC{slash}CN11{slash}RG9-Pad8)") (class "Default")
      (node (ref "U1") (pin "8") (pinfunction "RP27/PMA2/C2INC/CN11/RG9_8") (pintype "bidirectional"))
    )
    (net (code "86") (name "unconnected-(U1A-RP29{slash}PMA0{slash}AN15{slash}REFO{slash}CN12{slash}RB15-Pad30)") (class "Default")
      (node (ref "U1") (pin "30") (pinfunction "RP29/PMA0/AN15/REFO/CN12/RB15_30") (pintype "bidirectional"))
    )
    (net (code "87") (name "unconnected-(U1A-RP137{slash}SOSCO{slash}C3INC{slash}TICK{slash}CN0{slash}RC14-Pad48)") (class "Default")
      (node (ref "U1") (pin "48") (pinfunction "RP137/SOSCO/C3INC/TICK/CN0/RC14_48") (pintype "bidirectional"))
    )
    (net (code "88") (name "unconnected-(U1A-SOSCI{slash}C3IND{slash}CN1{slash}RC13-Pad47)") (class "Default")
      (node (ref "U1") (pin "47") (pinfunction "SOSCI/C3IND/CN1/RC13_47") (pintype "bidirectional"))
    )
    (net (code "89") (name "unconnected-(U1A-TCK{slash}PMA11{slash}AN12{slash}CTED2{slash}CN30{slash}RB12-Pad27)") (class "Default")
      (node (ref "U1") (pin "27") (pinfunction "TCK/PMA11/AN12/CTED2/CN30/RB12_27") (pintype "bidirectional"))
    )
    (net (code "90") (name "unconnected-(U1A-TDI{slash}PMA10{slash}AN13{slash}CTED1{slash}CN31{slash}RB13-Pad28)") (class "Default")
      (node (ref "U1") (pin "28") (pinfunction "TDI/PMA10/AN13/CTED1/CN31/RB13_28") (pintype "bidirectional"))
    )
    (net (code "91") (name "unconnected-(U1A-VBUSST{slash}VCMPST1{slash}CN68{slash}RF0-Pad58)") (class "Default")
      (node (ref "U1") (pin "58") (pinfunction "VBUSST/VCMPST1/CN68/RF0_58") (pintype "bidirectional"))
    )
    (net (code "92") (name "unconnected-(U1A-VCMPST2{slash}CN69{slash}RF1-Pad59)") (class "Default")
      (node (ref "U1") (pin "59") (pinfunction "VCMPST2/CN69/RF1_59") (pintype "bidirectional"))
    )
    (net (code "93") (name "unconnected-(U1A-VMIO{slash}RP13{slash}C2INB{slash}AN2{slash}CN4{slash}RB2-Pad14)") (class "Default")
      (node (ref "U1") (pin "14") (pinfunction "VMIO/RP13/C2INB/AN2/CN4/RB2_14") (pintype "bidirectional"))
    )
    (net (code "94") (name "unconnected-(U1A-VPIO{slash}C2INA{slash}AN3{slash}CN5{slash}RB3-Pad13)") (class "Default")
      (node (ref "U1") (pin "13") (pinfunction "VPIO/C2INA/AN3/CN5/RB3_13") (pintype "bidirectional"))
    )
  )
)
